# turbo2.net
KiCad netlist of a schematic drawn in EAGLE
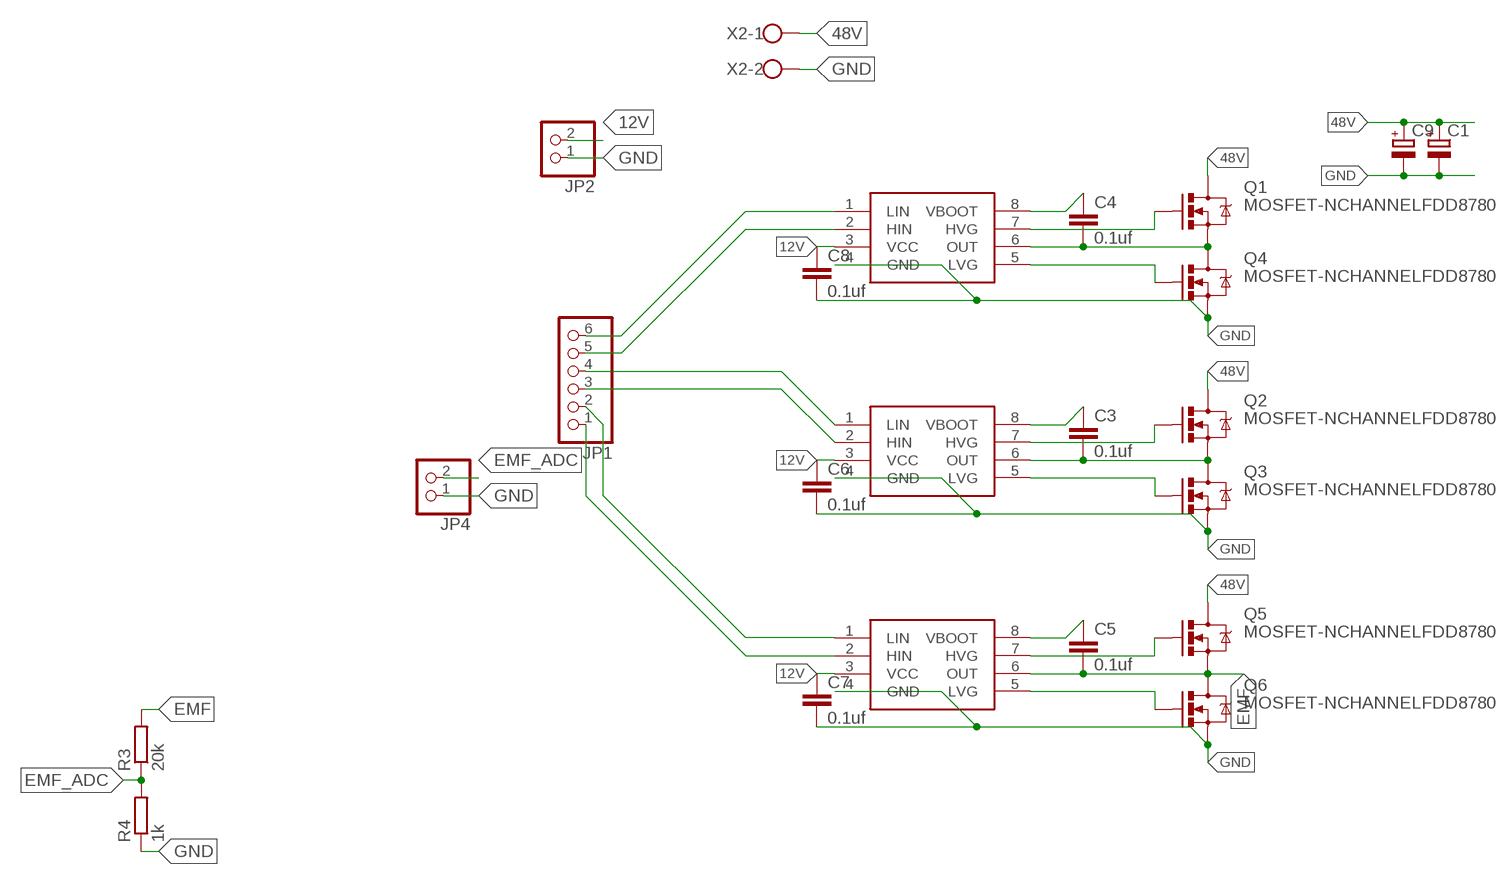
[diagram p0: schematic, sheet 1]

(export (version "E")
  (design (tool "Eeschema 10.0.6"))
  (components
    (comp (ref "C1")
      (value "CPOL-EUE5-8.5")
      (footprint "eagle-import:E5-8,5")
      (libsource (lib "eagle-import") (part "CPOL-EUE5-8.5"))
    )
    (comp (ref "C3")
      (value "0.1uf")
      (footprint "eagle-import:C0603")
      (libsource (lib "eagle-import") (part "C-EUC0603"))
    )
    (comp (ref "C4")
      (value "0.1uf")
      (footprint "eagle-import:C0603")
      (libsource (lib "eagle-import") (part "C-EUC0603"))
    )
    (comp (ref "C5")
      (value "0.1uf")
      (footprint "eagle-import:C0603")
      (libsource (lib "eagle-import") (part "C-EUC0603"))
    )
    (comp (ref "C6")
      (value "0.1uf")
      (footprint "eagle-import:C0603")
      (libsource (lib "eagle-import") (part "C-EUC0603"))
    )
    (comp (ref "C7")
      (value "0.1uf")
      (footprint "eagle-import:C0603")
      (libsource (lib "eagle-import") (part "C-EUC0603"))
    )
    (comp (ref "C8")
      (value "0.1uf")
      (footprint "eagle-import:C0603")
      (libsource (lib "eagle-import") (part "C-EUC0603"))
    )
    (comp (ref "C9")
      (value "CPOL-EUE5-8.5")
      (footprint "eagle-import:E5-8,5")
      (libsource (lib "eagle-import") (part "CPOL-EUE5-8.5"))
    )
    (comp (ref "JP1")
      (value "PINHD-1X6")
      (footprint "eagle-import:1X06")
      (libsource (lib "eagle-import") (part "PINHD-1X6"))
    )
    (comp (ref "JP2")
      (value "PINHD-1X2")
      (footprint "eagle-import:1X02")
      (libsource (lib "eagle-import") (part "PINHD-1X2"))
    )
    (comp (ref "JP4")
      (value "PINHD-1X2")
      (footprint "eagle-import:1X02")
      (libsource (lib "eagle-import") (part "PINHD-1X2"))
    )
    (comp (ref "Q1")
      (value "MOSFET-NCHANNELFDD8780")
      (footprint "eagle-import:DPAK")
      (libsource (lib "eagle-import") (part "MOSFET-NCHANNELFDD8780"))
    )
    (comp (ref "Q2")
      (value "MOSFET-NCHANNELFDD8780")
      (footprint "eagle-import:DPAK")
      (libsource (lib "eagle-import") (part "MOSFET-NCHANNELFDD8780"))
    )
    (comp (ref "Q3")
      (value "MOSFET-NCHANNELFDD8780")
      (footprint "eagle-import:DPAK")
      (libsource (lib "eagle-import") (part "MOSFET-NCHANNELFDD8780"))
    )
    (comp (ref "Q4")
      (value "MOSFET-NCHANNELFDD8780")
      (footprint "eagle-import:DPAK")
      (libsource (lib "eagle-import") (part "MOSFET-NCHANNELFDD8780"))
    )
    (comp (ref "Q5")
      (value "MOSFET-NCHANNELFDD8780")
      (footprint "eagle-import:DPAK")
      (libsource (lib "eagle-import") (part "MOSFET-NCHANNELFDD8780"))
    )
    (comp (ref "Q6")
      (value "MOSFET-NCHANNELFDD8780")
      (footprint "eagle-import:DPAK")
      (libsource (lib "eagle-import") (part "MOSFET-NCHANNELFDD8780"))
    )
    (comp (ref "R3")
      (value "20k")
      (footprint "eagle-import:R0603")
      (libsource (lib "eagle-import") (part "R-EU_R0603"))
    )
    (comp (ref "R4")
      (value "1k")
      (footprint "eagle-import:R0603")
      (libsource (lib "eagle-import") (part "R-EU_R0603"))
    )
    (comp (ref "U$1")
      (value "L6387")
      (footprint "eagle-import:SOIC8")
      (libsource (lib "eagle-import") (part "L6387"))
    )
    (comp (ref "U$2")
      (value "L6387")
      (footprint "eagle-import:SOIC8")
      (libsource (lib "eagle-import") (part "L6387"))
    )
    (comp (ref "U$3")
      (value "L6387")
      (footprint "eagle-import:SOIC8")
      (libsource (lib "eagle-import") (part "L6387"))
    )
    (comp (ref "X2")
      (value "W237-102")
      (footprint "eagle-import:W237-102")
      (fields (field (name "MPN") "237-102"))
      (libsource (lib "eagle-import") (part "W237-102"))
    )
  )
  (nets
    (net (code "1") (name "12V") (class "Default")
      (node (ref "C6") (pin "1") (pinfunction "1_1") (pintype "passive"))
      (node (ref "C7") (pin "1") (pinfunction "1_1") (pintype "passive"))
      (node (ref "C8") (pin "1") (pinfunction "1_1") (pintype "passive"))
      (node (ref "JP2") (pin "2") (pinfunction "2_2") (pintype "passive"))
      (node (ref "U$1") (pin "3") (pinfunction "VCC_3") (pintype "bidirectional"))
      (node (ref "U$2") (pin "3") (pinfunction "VCC_3") (pintype "bidirectional"))
      (node (ref "U$3") (pin "3") (pinfunction "VCC_3") (pintype "bidirectional"))
    )
    (net (code "2") (name "48V") (class "Default")
      (node (ref "C1") (pin "+") (pinfunction "+_+") (pintype "passive"))
      (node (ref "C9") (pin "+") (pinfunction "+_+") (pintype "passive"))
      (node (ref "Q1") (pin "4") (pinfunction "D_4") (pintype "passive"))
      (node (ref "Q2") (pin "4") (pinfunction "D_4") (pintype "passive"))
      (node (ref "Q5") (pin "4") (pinfunction "D_4") (pintype "passive"))
      (node (ref "X2") (pin "1") (pinfunction "KL_1") (pintype "passive"))
    )
    (net (code "3") (name "EMF") (class "Default")
      (node (ref "C5") (pin "2") (pinfunction "2_2") (pintype "passive"))
      (node (ref "Q5") (pin "3") (pinfunction "S_3") (pintype "passive"))
      (node (ref "Q6") (pin "4") (pinfunction "D_4") (pintype "passive"))
      (node (ref "R3") (pin "2") (pinfunction "2_2") (pintype "passive"))
      (node (ref "U$3") (pin "6") (pinfunction "OUT_6") (pintype "bidirectional"))
    )
    (net (code "4") (name "EMF_ADC") (class "Default")
      (node (ref "JP4") (pin "2") (pinfunction "2_2") (pintype "passive"))
      (node (ref "R3") (pin "1") (pinfunction "1_1") (pintype "passive"))
      (node (ref "R4") (pin "2") (pinfunction "2_2") (pintype "passive"))
    )
    (net (code "5") (name "GND") (class "Default")
      (node (ref "C1") (pin "-") (pinfunction "-_-") (pintype "passive"))
      (node (ref "C6") (pin "2") (pinfunction "2_2") (pintype "passive"))
      (node (ref "C7") (pin "2") (pinfunction "2_2") (pintype "passive"))
      (node (ref "C8") (pin "2") (pinfunction "2_2") (pintype "passive"))
      (node (ref "C9") (pin "-") (pinfunction "-_-") (pintype "passive"))
      (node (ref "JP2") (pin "1") (pinfunction "1_1") (pintype "passive"))
      (node (ref "JP4") (pin "1") (pinfunction "1_1") (pintype "passive"))
      (node (ref "Q3") (pin "3") (pinfunction "S_3") (pintype "passive"))
      (node (ref "Q4") (pin "3") (pinfunction "S_3") (pintype "passive"))
      (node (ref "Q6") (pin "3") (pinfunction "S_3") (pintype "passive"))
      (node (ref "R4") (pin "1") (pinfunction "1_1") (pintype "passive"))
      (node (ref "U$1") (pin "4") (pinfunction "GND_4") (pintype "bidirectional"))
      (node (ref "U$2") (pin "4") (pinfunction "GND_4") (pintype "bidirectional"))
      (node (ref "U$3") (pin "4") (pinfunction "GND_4") (pintype "bidirectional"))
      (node (ref "X2") (pin "2") (pinfunction "KL_2") (pintype "passive"))
    )
    (net (code "6") (name "Net-(Q1-G)") (class "Default")
      (node (ref "Q1") (pin "1") (pinfunction "G_1") (pintype "passive"))
      (node (ref "U$1") (pin "7") (pinfunction "HVG_7") (pintype "bidirectional"))
    )
    (net (code "7") (name "Net-(Q1-S)") (class "Default")
      (node (ref "C4") (pin "2") (pinfunction "2_2") (pintype "passive"))
      (node (ref "Q1") (pin "3") (pinfunction "S_3") (pintype "passive"))
      (node (ref "Q4") (pin "4") (pinfunction "D_4") (pintype "passive"))
      (node (ref "U$1") (pin "6") (pinfunction "OUT_6") (pintype "bidirectional"))
    )
    (net (code "8") (name "Net-(Q2-G)") (class "Default")
      (node (ref "Q2") (pin "1") (pinfunction "G_1") (pintype "passive"))
      (node (ref "U$2") (pin "7") (pinfunction "HVG_7") (pintype "bidirectional"))
    )
    (net (code "9") (name "Net-(Q2-S)") (class "Default")
      (node (ref "C3") (pin "2") (pinfunction "2_2") (pintype "passive"))
      (node (ref "Q2") (pin "3") (pinfunction "S_3") (pintype "passive"))
      (node (ref "Q3") (pin "4") (pinfunction "D_4") (pintype "passive"))
      (node (ref "U$2") (pin "6") (pinfunction "OUT_6") (pintype "bidirectional"))
    )
    (net (code "10") (name "Net-(Q3-G)") (class "Default")
      (node (ref "Q3") (pin "1") (pinfunction "G_1") (pintype "passive"))
      (node (ref "U$2") (pin "5") (pinfunction "LVG_5") (pintype "bidirectional"))
    )
    (net (code "11") (name "Net-(Q4-G)") (class "Default")
      (node (ref "Q4") (pin "1") (pinfunction "G_1") (pintype "passive"))
      (node (ref "U$1") (pin "5") (pinfunction "LVG_5") (pintype "bidirectional"))
    )
    (net (code "12") (name "Net-(Q5-G)") (class "Default")
      (node (ref "Q5") (pin "1") (pinfunction "G_1") (pintype "passive"))
      (node (ref "U$3") (pin "7") (pinfunction "HVG_7") (pintype "bidirectional"))
    )
    (net (code "13") (name "Net-(Q6-G)") (class "Default")
      (node (ref "Q6") (pin "1") (pinfunction "G_1") (pintype "passive"))
      (node (ref "U$3") (pin "5") (pinfunction "LVG_5") (pintype "bidirectional"))
    )
    (net (code "14") (name "Net-(U$1-HIN)") (class "Default")
      (node (ref "JP1") (pin "5") (pinfunction "5_5") (pintype "passive"))
      (node (ref "U$1") (pin "2") (pinfunction "HIN_2") (pintype "bidirectional"))
    )
    (net (code "15") (name "Net-(U$1-LIN)") (class "Default")
      (node (ref "JP1") (pin "6") (pinfunction "6_6") (pintype "passive"))
      (node (ref "U$1") (pin "1") (pinfunction "LIN_1") (pintype "bidirectional"))
    )
    (net (code "16") (name "Net-(U$1-VBOOT)") (class "Default")
      (node (ref "C4") (pin "1") (pinfunction "1_1") (pintype "passive"))
      (node (ref "U$1") (pin "8") (pinfunction "VBOOT_8") (pintype "bidirectional"))
    )
    (net (code "17") (name "Net-(U$2-HIN)") (class "Default")
      (node (ref "JP1") (pin "3") (pinfunction "3_3") (pintype "passive"))
      (node (ref "U$2") (pin "2") (pinfunction "HIN_2") (pintype "bidirectional"))
    )
    (net (code "18") (name "Net-(U$2-LIN)") (class "Default")
      (node (ref "JP1") (pin "4") (pinfunction "4_4") (pintype "passive"))
      (node (ref "U$2") (pin "1") (pinfunction "LIN_1") (pintype "bidirectional"))
    )
    (net (code "19") (name "Net-(U$2-VBOOT)") (class "Default")
      (node (ref "C3") (pin "1") (pinfunction "1_1") (pintype "passive"))
      (node (ref "U$2") (pin "8") (pinfunction "VBOOT_8") (pintype "bidirectional"))
    )
    (net (code "20") (name "Net-(U$3-HIN)") (class "Default")
      (node (ref "JP1") (pin "1") (pinfunction "1_1") (pintype "passive"))
      (node (ref "U$3") (pin "2") (pinfunction "HIN_2") (pintype "bidirectional"))
    )
    (net (code "21") (name "Net-(U$3-LIN)") (class "Default")
      (node (ref "JP1") (pin "2") (pinfunction "2_2") (pintype "passive"))
      (node (ref "U$3") (pin "1") (pinfunction "LIN_1") (pintype "bidirectional"))
    )
    (net (code "22") (name "Net-(U$3-VBOOT)") (class "Default")
      (node (ref "C5") (pin "1") (pinfunction "1_1") (pintype "passive"))
      (node (ref "U$3") (pin "8") (pinfunction "VBOOT_8") (pintype "bidirectional"))
    )
  )
)
